# Batteries.net
KiCad netlist of a schematic drawn in Altium Designer
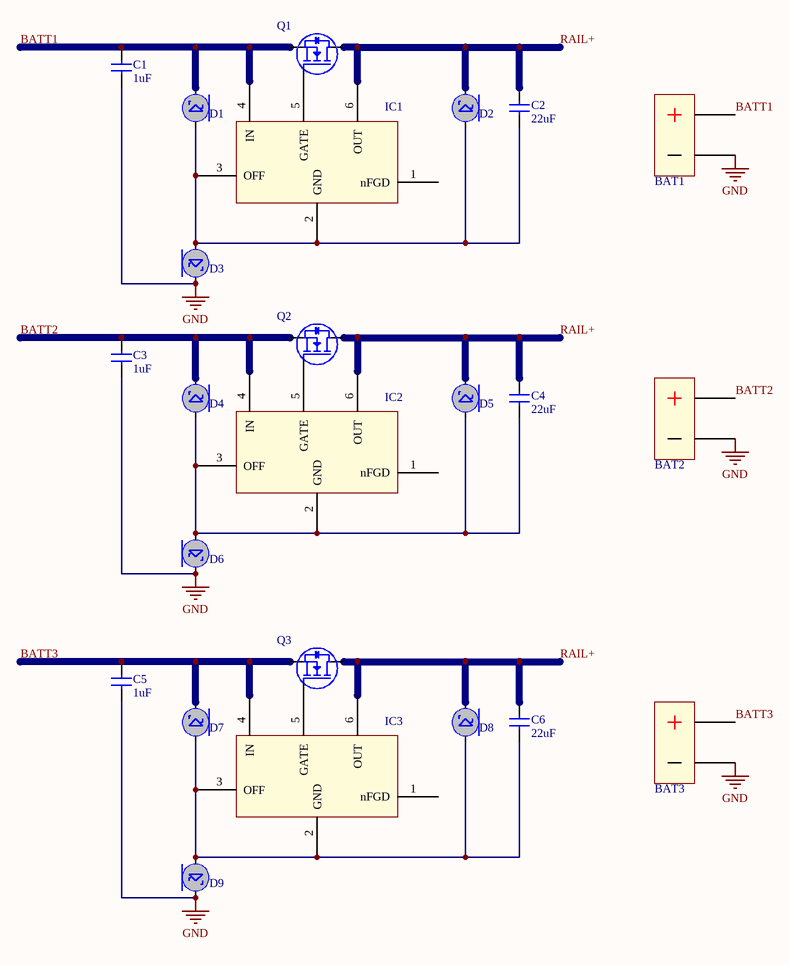
[diagram p0: Batteries.SchDoc]

(export (version "E")
  (design (tool "Eeschema 10.0.6"))
  (components
    (comp (ref "BAT1")
      (value "BATWIRE")
      (footprint "BATWIRE12")
      (description "Two large gauge leads soldered directly to the board.")
      (libsource (lib "Connectors") (part "BATWIRE"))
    )
    (comp (ref "BAT2")
      (value "BATWIRE")
      (footprint "BATWIRE12")
      (description "Two large gauge leads soldered directly to the board.")
      (libsource (lib "Connectors") (part "BATWIRE"))
    )
    (comp (ref "BAT3")
      (value "BATWIRE")
      (footprint "BATWIRE12")
      (description "Two large gauge leads soldered directly to the board.")
      (libsource (lib "Connectors") (part "BATWIRE"))
    )
    (comp (ref "C1")
      (value "1uF")
      (footprint "CAPC0603")
      (fields (field (name "Comment") "Cap"))
      (libsource (lib "Passives") (part "Cap"))
    )
    (comp (ref "C2")
      (value "22uF")
      (footprint "CAPC0603")
      (fields (field (name "Comment") "Cap"))
      (libsource (lib "Passives") (part "Cap"))
    )
    (comp (ref "C3")
      (value "1uF")
      (footprint "CAPC0603")
      (fields (field (name "Comment") "Cap"))
      (libsource (lib "Passives") (part "Cap"))
    )
    (comp (ref "C4")
      (value "22uF")
      (footprint "CAPC0603")
      (fields (field (name "Comment") "Cap"))
      (libsource (lib "Passives") (part "Cap"))
    )
    (comp (ref "C5")
      (value "1uF")
      (footprint "CAPC0603")
      (fields (field (name "Comment") "Cap"))
      (libsource (lib "Passives") (part "Cap"))
    )
    (comp (ref "C6")
      (value "22uF")
      (footprint "CAPC0603")
      (fields (field (name "Comment") "Cap"))
      (libsource (lib "Passives") (part "Cap"))
    )
    (comp (ref "D1")
      (value "SS16T3G")
      (footprint "SS16T3G")
      (description "DIODE SCHOTTKY 60V 1A SMA")
      (libsource (lib "Semiconductors") (part "SS16T3G"))
    )
    (comp (ref "D2")
      (value "SMBJ100A-13-F")
      (footprint "SMBJ100A-13-F")
      (description "TVS DIODE 100VWM 162VC SMB")
      (libsource (lib "Semiconductors") (part "SMBJ100A-13-F"))
    )
    (comp (ref "D3")
      (value "SS16T3G")
      (footprint "SS16T3G")
      (description "DIODE SCHOTTKY 60V 1A SMA")
      (libsource (lib "") (part "SS16T3G_1"))
    )
    (comp (ref "D4")
      (value "SS16T3G")
      (footprint "SS16T3G")
      (description "DIODE SCHOTTKY 60V 1A SMA")
      (libsource (lib "Semiconductors") (part "SS16T3G"))
    )
    (comp (ref "D5")
      (value "SMBJ100A-13-F")
      (footprint "SMBJ100A-13-F")
      (description "TVS DIODE 100VWM 162VC SMB")
      (libsource (lib "Semiconductors") (part "SMBJ100A-13-F"))
    )
    (comp (ref "D6")
      (value "SS16T3G")
      (footprint "SS16T3G")
      (description "DIODE SCHOTTKY 60V 1A SMA")
      (libsource (lib "") (part "SS16T3G_1"))
    )
    (comp (ref "D7")
      (value "SS16T3G")
      (footprint "SS110-TP")
      (description "DIODE SCHOTTKY 60V 1A SMA")
      (libsource (lib "Semiconductors") (part "SS16T3G"))
    )
    (comp (ref "D8")
      (value "SMBJ100A-13-F")
      (footprint "SMBJ100A-13-F")
      (description "TVS DIODE 100VWM 162VC SMB")
      (libsource (lib "Semiconductors") (part "SMBJ100A-13-F"))
    )
    (comp (ref "D9")
      (value "SS16T3G")
      (footprint "SS110-TP")
      (description "DIODE SCHOTTKY 60V 1A SMA")
      (libsource (lib "") (part "SS16T3G_1"))
    )
    (comp (ref "IC1")
      (value "LM5050MK-2/NOPB")
      (footprint "LM5050MK-2/NOPB")
      (description "IC OR CTRLR N+1 6SOT")
      (libsource (lib "ICs") (part "LM5050MK-2/NOPB"))
    )
    (comp (ref "IC2")
      (value "LM5050MK-2/NOPB")
      (footprint "LM5050MK-2/NOPB")
      (description "IC OR CTRLR N+1 6SOT")
      (libsource (lib "ICs") (part "LM5050MK-2/NOPB"))
    )
    (comp (ref "IC3")
      (value "LM5050MK-2/NOPB")
      (footprint "LM5050MK-2/NOPB")
      (description "IC OR CTRLR N+1 6SOT")
      (libsource (lib "ICs") (part "LM5050MK-2/NOPB"))
    )
    (comp (ref "Q1")
      (value "TPCA8052-H(TE12LQM")
      (footprint "TPCA8052-H(TE12LQM")
      (description "MOSFET N-CH 40V 20A 8SOP")
      (libsource (lib "Semiconductors") (part "TPCA8052-H"))
    )
    (comp (ref "Q2")
      (value "TPCA8052-H(TE12LQM")
      (footprint "TPCA8052-H(TE12LQM")
      (description "MOSFET N-CH 40V 20A 8SOP")
      (libsource (lib "Semiconductors") (part "TPCA8052-H"))
    )
    (comp (ref "Q3")
      (value "TPCA8052-H(TE12LQM")
      (footprint "TPCA8052-H(TE12LQM")
      (description "MOSFET N-CH 40V 20A 8SOP")
      (libsource (lib "Semiconductors") (part "TPCA8052-H"))
    )
  )
  (nets
    (net (code "1") (name "/BATT1") (class "Default")
      (node (ref "BAT1") (pin "+") (pinfunction "+_+") (pintype "power_in"))
      (node (ref "C1") (pin "1") (pinfunction "A_1") (pintype "passive"))
      (node (ref "D1") (pin "C") (pinfunction "C_C") (pintype "passive"))
      (node (ref "IC1") (pin "4") (pinfunction "IN_4") (pintype "passive"))
      (node (ref "Q1") (pin "S") (pinfunction "S_S") (pintype "passive"))
    )
    (net (code "2") (name "/BATT2") (class "Default")
      (node (ref "BAT2") (pin "+") (pinfunction "+_+") (pintype "power_in"))
      (node (ref "C3") (pin "1") (pinfunction "A_1") (pintype "passive"))
      (node (ref "D4") (pin "C") (pinfunction "C_C") (pintype "passive"))
      (node (ref "IC2") (pin "4") (pinfunction "IN_4") (pintype "passive"))
      (node (ref "Q2") (pin "S") (pinfunction "S_S") (pintype "passive"))
    )
    (net (code "3") (name "/BATT3") (class "Default")
      (node (ref "BAT3") (pin "+") (pinfunction "+_+") (pintype "power_in"))
      (node (ref "C5") (pin "1") (pinfunction "A_1") (pintype "passive"))
      (node (ref "D7") (pin "C") (pinfunction "C_C") (pintype "passive"))
      (node (ref "IC3") (pin "4") (pinfunction "IN_4") (pintype "passive"))
      (node (ref "Q3") (pin "S") (pinfunction "S_S") (pintype "passive"))
    )
    (net (code "4") (name "/RAIL+") (class "Default")
      (node (ref "C2") (pin "1") (pinfunction "A_1") (pintype "passive"))
      (node (ref "C4") (pin "1") (pinfunction "A_1") (pintype "passive"))
      (node (ref "C6") (pin "1") (pinfunction "A_1") (pintype "passive"))
      (node (ref "D2") (pin "C") (pinfunction "C_C") (pintype "passive"))
      (node (ref "D5") (pin "C") (pinfunction "C_C") (pintype "passive"))
      (node (ref "D8") (pin "C") (pinfunction "C_C") (pintype "passive"))
      (node (ref "IC1") (pin "6") (pinfunction "OUT_6") (pintype "passive"))
      (node (ref "IC2") (pin "6") (pinfunction "OUT_6") (pintype "passive"))
      (node (ref "IC3") (pin "6") (pinfunction "OUT_6") (pintype "passive"))
      (node (ref "Q1") (pin "D") (pinfunction "D_D") (pintype "passive"))
      (node (ref "Q2") (pin "D") (pinfunction "D_D") (pintype "passive"))
      (node (ref "Q3") (pin "D") (pinfunction "D_D") (pintype "passive"))
    )
    (net (code "5") (name "GND") (class "Default")
      (node (ref "BAT1") (pin "-") (pinfunction "-_-") (pintype "power_in"))
      (node (ref "BAT2") (pin "-") (pinfunction "-_-") (pintype "power_in"))
      (node (ref "BAT3") (pin "-") (pinfunction "-_-") (pintype "power_in"))
      (node (ref "C1") (pin "2") (pinfunction "B_2") (pintype "passive"))
      (node (ref "C3") (pin "2") (pinfunction "B_2") (pintype "passive"))
      (node (ref "C5") (pin "2") (pinfunction "B_2") (pintype "passive"))
      (node (ref "D3") (pin "C") (pinfunction "C_C") (pintype "passive"))
      (node (ref "D6") (pin "C") (pinfunction "C_C") (pintype "passive"))
      (node (ref "D9") (pin "C") (pinfunction "C_C") (pintype "passive"))
    )
    (net (code "6") (name "Net-(C2-B)") (class "Default")
      (node (ref "C2") (pin "2") (pinfunction "B_2") (pintype "passive"))
      (node (ref "D1") (pin "A") (pinfunction "A_A") (pintype "passive"))
      (node (ref "D2") (pin "A") (pinfunction "A_A") (pintype "passive"))
      (node (ref "D3") (pin "A") (pinfunction "A_A") (pintype "passive"))
      (node (ref "IC1") (pin "2") (pinfunction "GND_2") (pintype "passive"))
      (node (ref "IC1") (pin "3") (pinfunction "OFF_3") (pintype "passive"))
    )
    (net (code "7") (name "Net-(C4-B)") (class "Default")
      (node (ref "C4") (pin "2") (pinfunction "B_2") (pintype "passive"))
      (node (ref "D4") (pin "A") (pinfunction "A_A") (pintype "passive"))
      (node (ref "D5") (pin "A") (pinfunction "A_A") (pintype "passive"))
      (node (ref "D6") (pin "A") (pinfunction "A_A") (pintype "passive"))
      (node (ref "IC2") (pin "2") (pinfunction "GND_2") (pintype "passive"))
      (node (ref "IC2") (pin "3") (pinfunction "OFF_3") (pintype "passive"))
    )
    (net (code "8") (name "Net-(C6-B)") (class "Default")
      (node (ref "C6") (pin "2") (pinfunction "B_2") (pintype "passive"))
      (node (ref "D7") (pin "A") (pinfunction "A_A") (pintype "passive"))
      (node (ref "D8") (pin "A") (pinfunction "A_A") (pintype "passive"))
      (node (ref "D9") (pin "A") (pinfunction "A_A") (pintype "passive"))
      (node (ref "IC3") (pin "2") (pinfunction "GND_2") (pintype "passive"))
      (node (ref "IC3") (pin "3") (pinfunction "OFF_3") (pintype "passive"))
    )
    (net (code "9") (name "Net-(IC1-GATE)") (class "Default")
      (node (ref "IC1") (pin "5") (pinfunction "GATE_5") (pintype "passive"))
      (node (ref "Q1") (pin "G") (pinfunction "G_G") (pintype "passive"))
    )
    (net (code "10") (name "Net-(IC2-GATE)") (class "Default")
      (node (ref "IC2") (pin "5") (pinfunction "GATE_5") (pintype "passive"))
      (node (ref "Q2") (pin "G") (pinfunction "G_G") (pintype "passive"))
    )
    (net (code "11") (name "Net-(IC3-GATE)") (class "Default")
      (node (ref "IC3") (pin "5") (pinfunction "GATE_5") (pintype "passive"))
      (node (ref "Q3") (pin "G") (pinfunction "G_G") (pintype "passive"))
    )
    (net (code "12") (name "unconnected-(IC1-nFGD-Pad1)") (class "Default")
      (node (ref "IC1") (pin "1") (pinfunction "nFGD_1") (pintype "passive"))
    )
    (net (code "13") (name "unconnected-(IC2-nFGD-Pad1)") (class "Default")
      (node (ref "IC2") (pin "1") (pinfunction "nFGD_1") (pintype "passive"))
    )
    (net (code "14") (name "unconnected-(IC3-nFGD-Pad1)") (class "Default")
      (node (ref "IC3") (pin "1") (pinfunction "nFGD_1") (pintype "passive"))
    )
  )
)
